# ChakraPendant.net
KiCad netlist of a schematic drawn in EAGLE
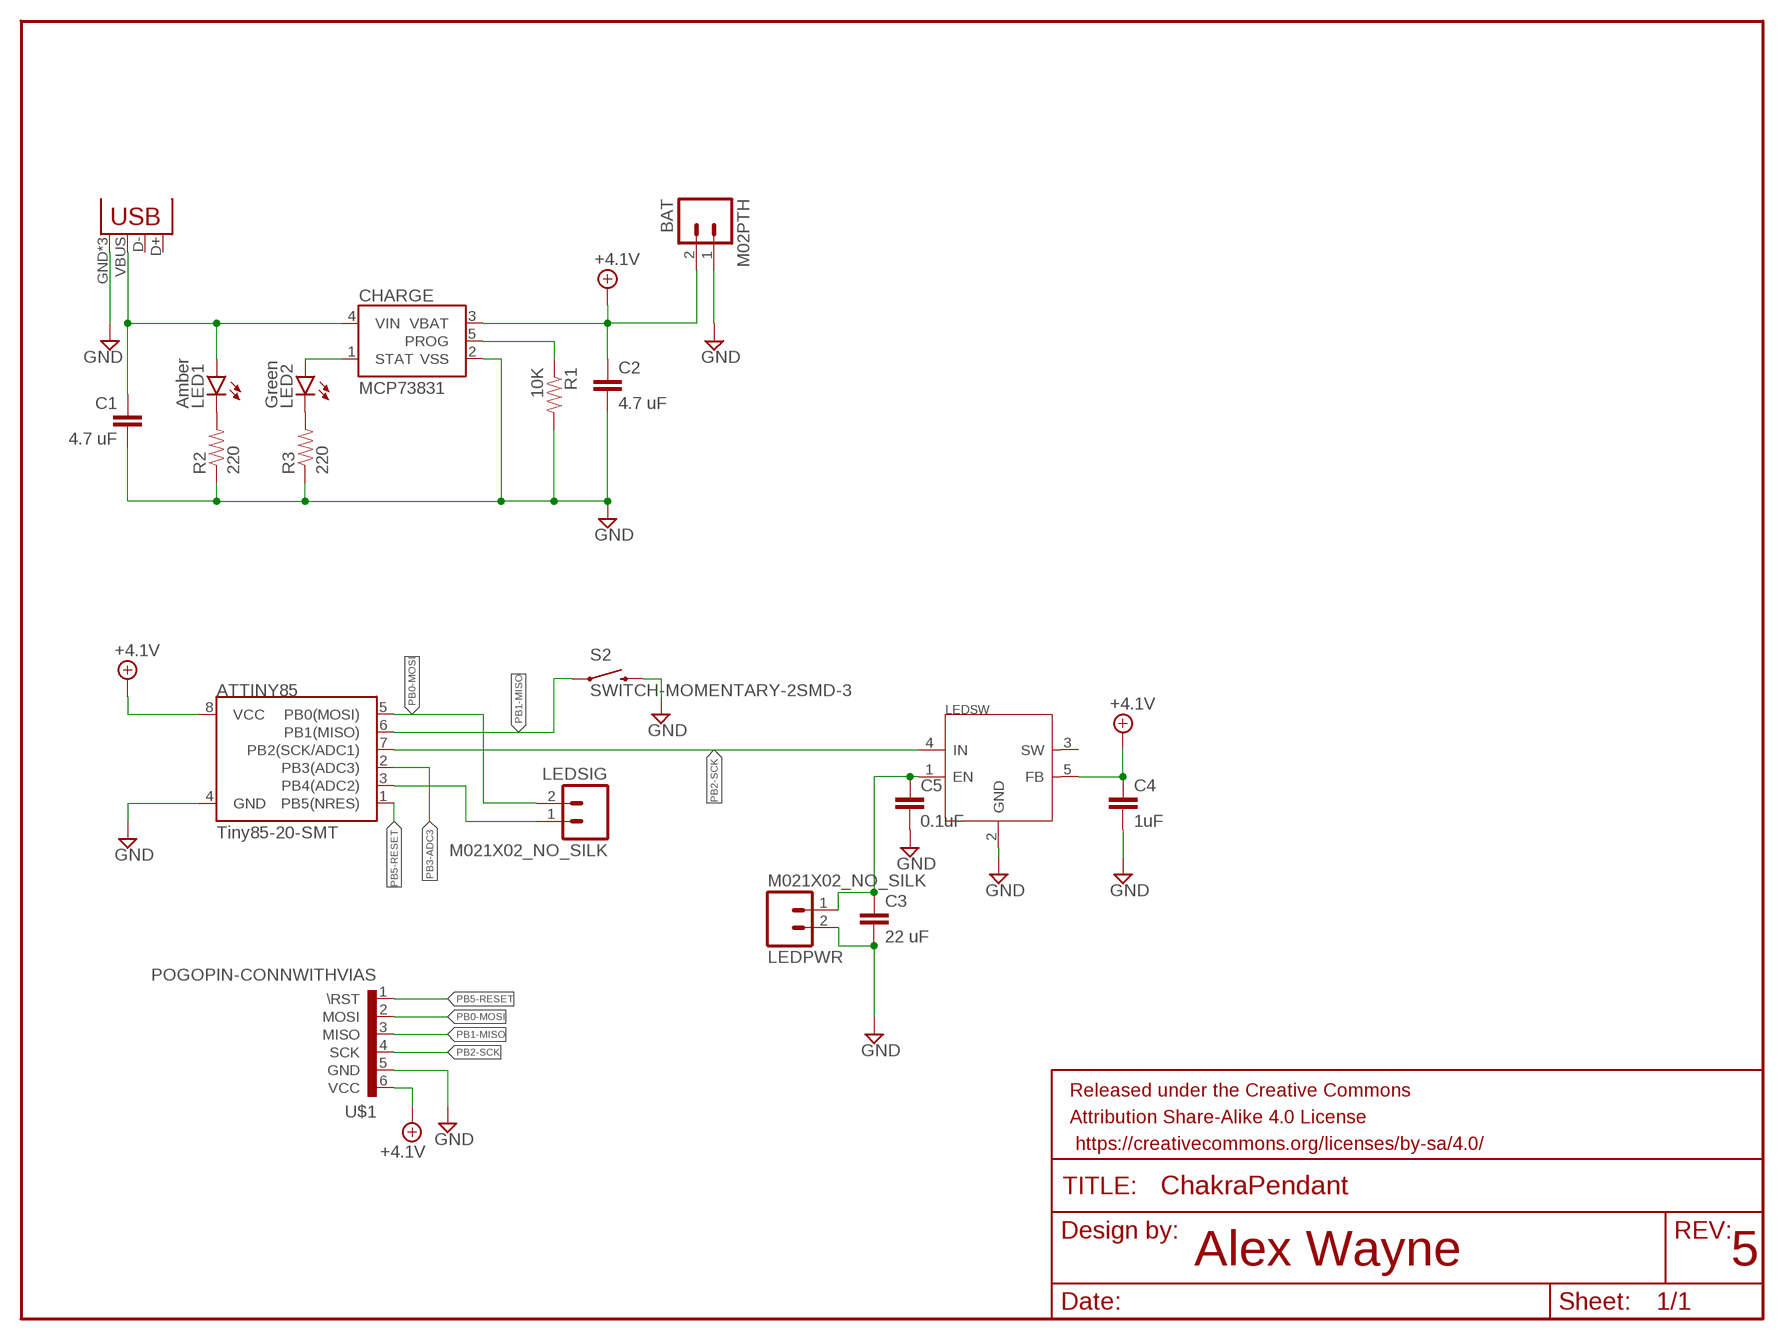
[diagram p0: schematic, sheet 1]

(export (version "E")
  (design (tool "Eeschema 10.0.6"))
  (components
    (comp (ref "ATTINY85")
      (value "Tiny85-20-SMT")
      (footprint "eagle-import:SO08-EIAJ")
      (libsource (lib "eagle-import") (part "ATTINY45TINY85-20-SMT"))
    )
    (comp (ref "BAT")
      (value "M02PTH")
      (footprint "eagle-import:1X02")
      (libsource (lib "eagle-import") (part "M02PTH"))
    )
    (comp (ref "C1")
      (value "4.7 uF")
      (footprint "eagle-import:0603-CAP")
      (libsource (lib "eagle-import") (part "CAP0603-CAP"))
    )
    (comp (ref "C2")
      (value "4.7 uF")
      (footprint "eagle-import:0603-CAP")
      (libsource (lib "eagle-import") (part "CAP0603-CAP"))
    )
    (comp (ref "C3")
      (value "22 uF")
      (footprint "eagle-import:1206")
      (libsource (lib "eagle-import") (part "CAP1206"))
    )
    (comp (ref "C4")
      (value "1uF")
      (footprint "eagle-import:0603-CAP")
      (libsource (lib "eagle-import") (part "CAP0603-CAP"))
    )
    (comp (ref "C5")
      (value "0.1uF")
      (footprint "eagle-import:0603-CAP")
      (libsource (lib "eagle-import") (part "CAP0603-CAP"))
    )
    (comp (ref "CHARGE")
      (value "MCP73831")
      (footprint "eagle-import:SOT23-5")
      (libsource (lib "eagle-import") (part "MCP73831"))
    )
    (comp (ref "FRAME1")
      (value "FRAME-LETTER")
      (footprint "eagle-import:CREATIVE_COMMONS")
      (libsource (lib "eagle-import") (part "FRAME-LETTER"))
    )
    (comp (ref "JP1")
      (value "USB-MICROB")
      (footprint "eagle-import:USB-MICROB")
      (libsource (lib "eagle-import") (part "USB-MICROB"))
    )
    (comp (ref "LED1")
      (value "Amber")
      (footprint "eagle-import:LED-0603")
      (libsource (lib "eagle-import") (part "LED0603"))
    )
    (comp (ref "LED2")
      (value "Green")
      (footprint "eagle-import:LED-0603")
      (libsource (lib "eagle-import") (part "LED0603"))
    )
    (comp (ref "LEDPWR")
      (value "M021X02_NO_SILK")
      (footprint "eagle-import:1X02_NO_SILK")
      (libsource (lib "eagle-import") (part "M021X02_NO_SILK"))
    )
    (comp (ref "LEDSIG")
      (value "M021X02_NO_SILK")
      (footprint "eagle-import:1X02_NO_SILK")
      (libsource (lib "eagle-import") (part "M021X02_NO_SILK"))
    )
    (comp (ref "LEDSW")
      (value "ETA3406")
      (footprint "eagle-import:SOT23-5")
      (libsource (lib "eagle-import") (part "ETA3406"))
    )
    (comp (ref "R1")
      (value "10K")
      (footprint "eagle-import:0603-RES")
      (libsource (lib "eagle-import") (part "RESISTOR0603-RES"))
    )
    (comp (ref "R2")
      (value "220")
      (footprint "eagle-import:0603-RES")
      (libsource (lib "eagle-import") (part "RESISTOR0603-RES"))
    )
    (comp (ref "R3")
      (value "220")
      (footprint "eagle-import:0603-RES")
      (libsource (lib "eagle-import") (part "RESISTOR0603-RES"))
    )
    (comp (ref "S2")
      (value "SWITCH-MOMENTARY-2SMD-3")
      (footprint "eagle-import:TACTILE_SWITCH_SMD-3")
      (libsource (lib "eagle-import") (part "SWITCH-MOMENTARY-2SMD-3"))
    )
    (comp (ref "U$1")
      (value "POGOPIN-CONNWITHVIAS")
      (footprint "eagle-import:POGOPROG-CONN-0H")
      (libsource (lib "eagle-import") (part "POGOPIN-CONNWITHVIAS"))
    )
  )
  (nets
    (net (code "1") (name "+4.1V") (class "Default")
      (node (ref "ATTINY85") (pin "8") (pinfunction "VCC_8") (pintype "bidirectional"))
      (node (ref "BAT") (pin "2") (pinfunction "2_2") (pintype "passive"))
      (node (ref "C2") (pin "1") (pinfunction "1_1") (pintype "passive"))
      (node (ref "C4") (pin "1") (pinfunction "1_1") (pintype "passive"))
      (node (ref "CHARGE") (pin "3") (pinfunction "VBAT_3") (pintype "power_in"))
      (node (ref "LEDSW") (pin "5") (pinfunction "FB_5") (pintype "bidirectional"))
      (node (ref "U$1") (pin "6") (pinfunction "VCC_6") (pintype "bidirectional"))
    )
    (net (code "2") (name "GND") (class "Default")
      (node (ref "ATTINY85") (pin "4") (pinfunction "GND_4") (pintype "bidirectional"))
      (node (ref "BAT") (pin "1") (pinfunction "1_1") (pintype "passive"))
      (node (ref "C1") (pin "2") (pinfunction "2_2") (pintype "passive"))
      (node (ref "C2") (pin "2") (pinfunction "2_2") (pintype "passive"))
      (node (ref "C3") (pin "2") (pinfunction "2_2") (pintype "passive"))
      (node (ref "C4") (pin "2") (pinfunction "2_2") (pintype "passive"))
      (node (ref "C5") (pin "2") (pinfunction "2_2") (pintype "passive"))
      (node (ref "CHARGE") (pin "2") (pinfunction "VSS_2") (pintype "power_in"))
      (node (ref "JP1") (pin "GND") (pinfunction "GND_GND") (pintype "bidirectional"))
      (node (ref "JP1") (pin "MT1") (pinfunction "GND_MT1") (pintype "bidirectional"))
      (node (ref "JP1") (pin "MT2") (pinfunction "GND_MT2") (pintype "bidirectional"))
      (node (ref "LEDPWR") (pin "2") (pinfunction "2_2") (pintype "passive"))
      (node (ref "LEDSW") (pin "2") (pinfunction "GND_2") (pintype "bidirectional"))
      (node (ref "R1") (pin "2") (pinfunction "2_2") (pintype "passive"))
      (node (ref "R2") (pin "1") (pinfunction "1_1") (pintype "passive"))
      (node (ref "R3") (pin "1") (pinfunction "1_1") (pintype "passive"))
      (node (ref "S2") (pin "4") (pinfunction "2_4") (pintype "passive"))
      (node (ref "U$1") (pin "5") (pinfunction "GND_5") (pintype "bidirectional"))
    )
    (net (code "3") (name "Net-(ATTINY85-PB4(ADC2))") (class "Default")
      (node (ref "ATTINY85") (pin "3") (pinfunction "PB4(ADC2)_3") (pintype "bidirectional"))
      (node (ref "LEDSIG") (pin "1") (pinfunction "1_1") (pintype "passive"))
    )
    (net (code "4") (name "Net-(CHARGE-PROG)") (class "Default")
      (node (ref "CHARGE") (pin "5") (pinfunction "PROG_5") (pintype "input"))
      (node (ref "R1") (pin "1") (pinfunction "1_1") (pintype "passive"))
    )
    (net (code "5") (name "Net-(CHARGE-STAT)") (class "Default")
      (node (ref "CHARGE") (pin "1") (pinfunction "STAT_1") (pintype "output"))
      (node (ref "LED2") (pin "A") (pinfunction "A_A") (pintype "passive"))
    )
    (net (code "6") (name "Net-(CHARGE-VIN)") (class "Default")
      (node (ref "C1") (pin "1") (pinfunction "1_1") (pintype "passive"))
      (node (ref "CHARGE") (pin "4") (pinfunction "VIN_4") (pintype "power_in"))
      (node (ref "JP1") (pin "VBUS") (pinfunction "VBUS_VBUS") (pintype "bidirectional"))
      (node (ref "LED1") (pin "A") (pinfunction "A_A") (pintype "passive"))
    )
    (net (code "7") (name "Net-(LED1-PadC)") (class "Default")
      (node (ref "LED1") (pin "C") (pinfunction "C_C") (pintype "passive"))
      (node (ref "R2") (pin "2") (pinfunction "2_2") (pintype "passive"))
    )
    (net (code "8") (name "Net-(LED2-PadC)") (class "Default")
      (node (ref "LED2") (pin "C") (pinfunction "C_C") (pintype "passive"))
      (node (ref "R3") (pin "2") (pinfunction "2_2") (pintype "passive"))
    )
    (net (code "9") (name "Net-(LEDSW-EN)") (class "Default")
      (node (ref "C3") (pin "1") (pinfunction "1_1") (pintype "passive"))
      (node (ref "C5") (pin "1") (pinfunction "1_1") (pintype "passive"))
      (node (ref "LEDPWR") (pin "1") (pinfunction "1_1") (pintype "passive"))
      (node (ref "LEDSW") (pin "1") (pinfunction "EN_1") (pintype "bidirectional"))
    )
    (net (code "10") (name "PB0-MOSI") (class "Default")
      (node (ref "ATTINY85") (pin "5") (pinfunction "PB0(MOSI)_5") (pintype "bidirectional"))
      (node (ref "LEDSIG") (pin "2") (pinfunction "2_2") (pintype "passive"))
      (node (ref "U$1") (pin "2") (pinfunction "MOSI_2") (pintype "bidirectional"))
    )
    (net (code "11") (name "PB1-MISO") (class "Default")
      (node (ref "ATTINY85") (pin "6") (pinfunction "PB1(MISO)_6") (pintype "bidirectional"))
      (node (ref "S2") (pin "1") (pinfunction "1_1") (pintype "passive"))
      (node (ref "U$1") (pin "3") (pinfunction "MISO_3") (pintype "bidirectional"))
    )
    (net (code "12") (name "PB2-SCK") (class "Default")
      (node (ref "ATTINY85") (pin "7") (pinfunction "PB2(SCK/ADC1)_7") (pintype "bidirectional"))
      (node (ref "LEDSW") (pin "4") (pinfunction "IN_4") (pintype "bidirectional"))
      (node (ref "U$1") (pin "4") (pinfunction "SCK_4") (pintype "bidirectional"))
    )
    (net (code "13") (name "PB3-ADC3") (class "Default")
      (node (ref "ATTINY85") (pin "2") (pinfunction "PB3(ADC3)_2") (pintype "bidirectional"))
    )
    (net (code "14") (name "PB5-RESET") (class "Default")
      (node (ref "ATTINY85") (pin "1") (pinfunction "PB5(NRES)_1") (pintype "bidirectional"))
      (node (ref "U$1") (pin "1") (pinfunction "\\RST_1") (pintype "bidirectional"))
    )
    (net (code "15") (name "unconnected-(JP1-PadD+)") (class "Default")
      (node (ref "JP1") (pin "D+") (pinfunction "D+_D+") (pintype "bidirectional"))
    )
    (net (code "16") (name "unconnected-(JP1-PadD-)") (class "Default")
      (node (ref "JP1") (pin "D-") (pinfunction "D-_D-") (pintype "bidirectional"))
    )
    (net (code "17") (name "unconnected-(LEDSW-SW-Pad3)") (class "Default")
      (node (ref "LEDSW") (pin "3") (pinfunction "SW_3") (pintype "bidirectional"))
    )
  )
)
